# Mini-MLL_Plus_v0_3.net
KiCad netlist of a schematic drawn in EAGLE
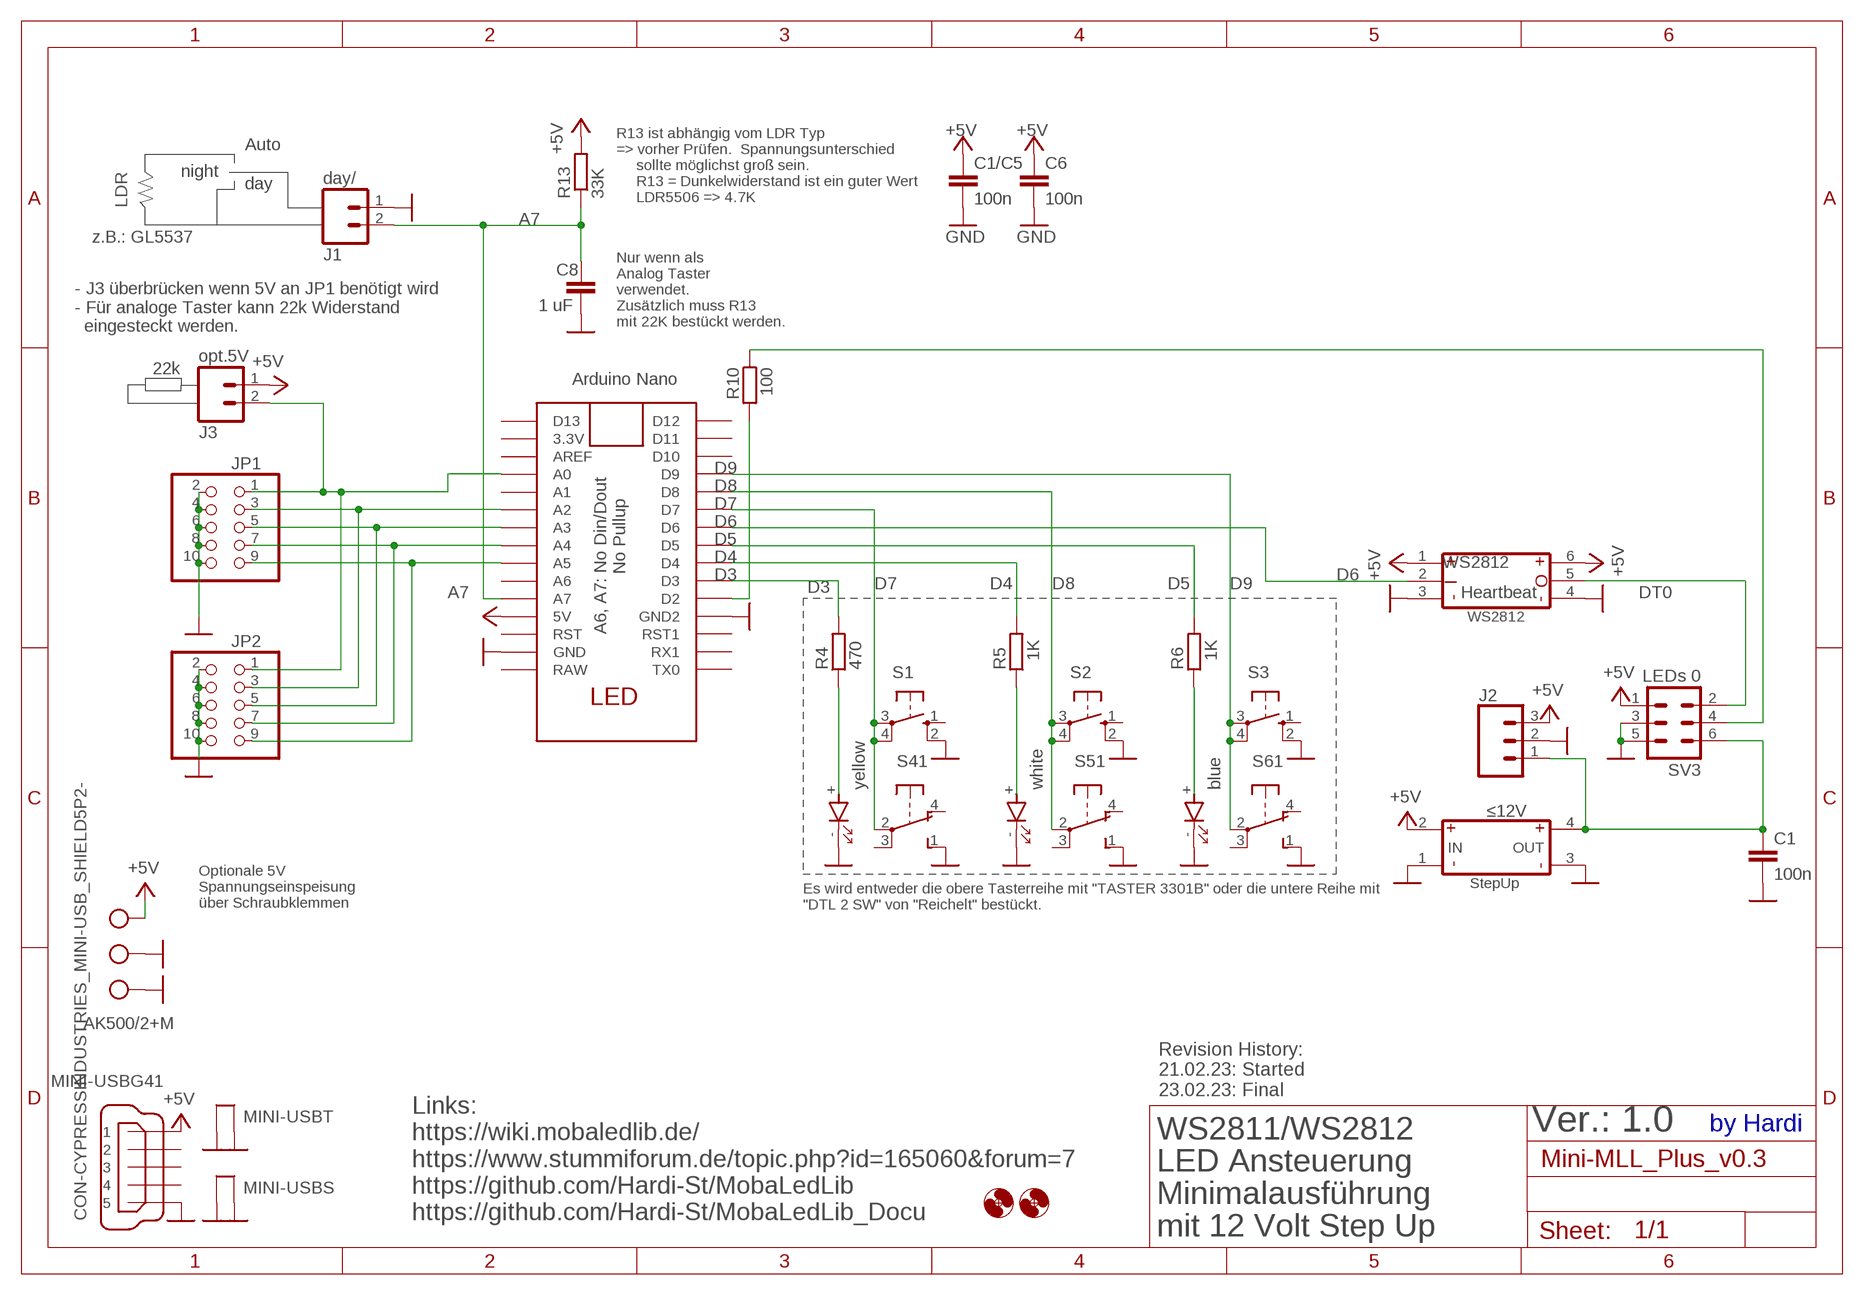
[diagram p0: schematic, sheet 1]

(export (version "E")
  (design (tool "Eeschema 10.0.6"))
  (components
    (comp (ref "C1")
      (value "100n")
      (footprint "eagle-import:C025-025X050")
      (libsource (lib "eagle-import") (part "C-EU025-025X050"))
    )
    (comp (ref "C1/C5")
      (value "100n")
      (footprint "eagle-import:C025-025X050")
      (libsource (lib "eagle-import") (part "C-EU025-025X050"))
    )
    (comp (ref "C6")
      (value "100n")
      (footprint "eagle-import:C025-025X050")
      (libsource (lib "eagle-import") (part "C-EU025-025X050"))
    )
    (comp (ref "C8")
      (value "1 uF")
      (footprint "eagle-import:C025-025X050")
      (libsource (lib "eagle-import") (part "C-EU025-025X050"))
    )
    (comp (ref "H1")
      (value "MOUNT-HOLE3.0")
      (footprint "eagle-import:3,0")
      (libsource (lib "eagle-import") (part "MOUNT-HOLE3.0"))
    )
    (comp (ref "H2")
      (value "MOUNT-HOLE3.0")
      (footprint "eagle-import:3,0")
      (libsource (lib "eagle-import") (part "MOUNT-HOLE3.0"))
    )
    (comp (ref "J1")
      (value "day/")
      (footprint "eagle-import:1X02")
      (libsource (lib "eagle-import") (part "M02PTH"))
    )
    (comp (ref "J2")
      (value "CONN_03")
      (footprint "eagle-import:1X03")
      (libsource (lib "eagle-import") (part "CONN_03"))
    )
    (comp (ref "J3")
      (value "opt.5V")
      (footprint "eagle-import:1X02")
      (libsource (lib "eagle-import") (part "M02PTH"))
    )
    (comp (ref "JP1")
      (value "PINHD-2X5/90")
      (footprint "eagle-import:2X05_90")
      (libsource (lib "eagle-import") (part "PINHD-2X5/90"))
    )
    (comp (ref "JP2")
      (value "PINHD-2X5CLEAR")
      (footprint "eagle-import:2X05_90_CL")
      (libsource (lib "eagle-import") (part "PINHD-2X5CLEAR"))
    )
    (comp (ref "MINI-USB")
      (value "CON-CYPRESSINDUSTRIES_MINI-USB_SHIELD5P2-")
      (footprint "eagle-import:MINI_USB_MULTI")
      (libsource (lib "eagle-import") (part "CON-CYPRESSINDUSTRIES_MINI-USB_SHIELD5P2-"))
    )
    (comp (ref "R4")
      (value "470")
      (footprint "eagle-import:0204_7")
      (libsource (lib "eagle-import") (part "R0204/7"))
    )
    (comp (ref "R5")
      (value "1K")
      (footprint "eagle-import:0204_7")
      (libsource (lib "eagle-import") (part "R0204/7"))
    )
    (comp (ref "R6")
      (value "1K")
      (footprint "eagle-import:0204_7")
      (libsource (lib "eagle-import") (part "R0204/7"))
    )
    (comp (ref "R10")
      (value "100")
      (footprint "eagle-import:0207_2V")
      (libsource (lib "eagle-import") (part "R-EU_0207/2V"))
    )
    (comp (ref "R13")
      (value "33K")
      (footprint "eagle-import:0204_7")
      (libsource (lib "eagle-import") (part "R0204/7"))
    )
    (comp (ref "S1")
      (value "10-XX")
      (footprint "eagle-import:B3F-10XX")
      (fields (field (name "MPN") "B3F-1000"))
      (libsource (lib "eagle-import") (part "10-XX"))
    )
    (comp (ref "S2")
      (value "10-XX")
      (footprint "eagle-import:B3F-10XX")
      (fields (field (name "MPN") "B3F-1000"))
      (libsource (lib "eagle-import") (part "10-XX"))
    )
    (comp (ref "S3")
      (value "10-XX")
      (footprint "eagle-import:B3F-10XX")
      (fields (field (name "MPN") "B3F-1000"))
      (libsource (lib "eagle-import") (part "10-XX"))
    )
    (comp (ref "S4")
      (value "yellow")
      (footprint "eagle-import:SRKL")
      (libsource (lib "eagle-import") (part "SRKL"))
    )
    (comp (ref "S5")
      (value "white")
      (footprint "eagle-import:SRKL")
      (libsource (lib "eagle-import") (part "SRKL"))
    )
    (comp (ref "S6")
      (value "blue")
      (footprint "eagle-import:SRKL")
      (libsource (lib "eagle-import") (part "SRKL"))
    )
    (comp (ref "SV3")
      (value "LEDs 0")
      (footprint "eagle-import:ML6")
      (libsource (lib "eagle-import") (part "ML6"))
    )
    (comp (ref "U2")
      (value "LED NANO")
      (footprint "eagle-import:NANO")
      (libsource (lib "eagle-import") (part "NANO"))
    )
    (comp (ref "WS2812")
      (value "WS2812_BREAKOUT")
      (footprint "eagle-import:WS2812__BREAKOUT")
      (libsource (lib "eagle-import") (part "WS2812_BREAKOUT"))
    )
    (comp (ref "X4")
      (value "AK500/2+M")
      (footprint "eagle-import:AK500_2+M")
      (libsource (lib "eagle-import") (part "AK500/2+M"))
    )
    (comp (ref "≤12V")
      (value "STEP_UP")
      (footprint "eagle-import:MINI_STEP_UP")
      (libsource (lib "eagle-import") (part "STEP_UP"))
    )
  )
  (nets
    (net (code "1") (name "+5V") (class "Default")
      (node (ref "C1/C5") (pin "1") (pinfunction "1_1") (pintype "passive"))
      (node (ref "C6") (pin "1") (pinfunction "1_1") (pintype "passive"))
      (node (ref "J2") (pin "3") (pinfunction "3_3") (pintype "passive"))
      (node (ref "J3") (pin "1") (pinfunction "1_1") (pintype "passive"))
      (node (ref "MINI-USB") (pin "1") (pinfunction "1_1") (pintype "passive"))
      (node (ref "R13") (pin "2") (pinfunction "2_2") (pintype "passive"))
      (node (ref "SV3") (pin "1") (pinfunction "1_1") (pintype "passive"))
      (node (ref "U2") (pin "5V") (pinfunction "5V_5V") (pintype "bidirectional"))
      (node (ref "WS2812") (pin "1") (pinfunction "VDD1_1") (pintype "passive"))
      (node (ref "WS2812") (pin "6") (pinfunction "VDD_6") (pintype "passive"))
      (node (ref "X4") (pin "2") (pinfunction "KL_2") (pintype "passive"))
      (node (ref "≤12V") (pin "2") (pinfunction "VDD_IN_2") (pintype "passive"))
    )
    (net (code "2") (name "/A7") (class "Default")
      (node (ref "C8") (pin "1") (pinfunction "1_1") (pintype "passive"))
      (node (ref "J1") (pin "2") (pinfunction "2_2") (pintype "passive"))
      (node (ref "R13") (pin "1") (pinfunction "1_1") (pintype "passive"))
      (node (ref "U2") (pin "A7") (pinfunction "A7_A7") (pintype "bidirectional"))
    )
    (net (code "3") (name "/D3") (class "Default")
      (node (ref "R4") (pin "2") (pinfunction "2_2") (pintype "passive"))
      (node (ref "U2") (pin "D3") (pinfunction "D3_D3") (pintype "bidirectional"))
    )
    (net (code "4") (name "/D4") (class "Default")
      (node (ref "R5") (pin "2") (pinfunction "2_2") (pintype "passive"))
      (node (ref "U2") (pin "D4") (pinfunction "D4_D4") (pintype "bidirectional"))
    )
    (net (code "5") (name "/D5") (class "Default")
      (node (ref "R6") (pin "2") (pinfunction "2_2") (pintype "passive"))
      (node (ref "U2") (pin "D5") (pinfunction "D5_D5") (pintype "bidirectional"))
    )
    (net (code "6") (name "/D6") (class "Default")
      (node (ref "U2") (pin "D6") (pinfunction "D6_D6") (pintype "bidirectional"))
      (node (ref "WS2812") (pin "2") (pinfunction "DIN_2") (pintype "passive"))
    )
    (net (code "7") (name "/D7") (class "Default")
      (node (ref "S1") (pin "3") (pinfunction "P_3") (pintype "passive"))
      (node (ref "S1") (pin "4") (pinfunction "P1_4") (pintype "passive"))
      (node (ref "S4") (pin "2") (pinfunction "P_2") (pintype "passive"))
      (node (ref "U2") (pin "D7") (pinfunction "D7_D7") (pintype "bidirectional"))
    )
    (net (code "8") (name "/D8") (class "Default")
      (node (ref "S2") (pin "3") (pinfunction "P_3") (pintype "passive"))
      (node (ref "S2") (pin "4") (pinfunction "P1_4") (pintype "passive"))
      (node (ref "S5") (pin "2") (pinfunction "P_2") (pintype "passive"))
      (node (ref "U2") (pin "D8") (pinfunction "D8_D8") (pintype "bidirectional"))
    )
    (net (code "9") (name "/D9") (class "Default")
      (node (ref "S3") (pin "3") (pinfunction "P_3") (pintype "passive"))
      (node (ref "S3") (pin "4") (pinfunction "P1_4") (pintype "passive"))
      (node (ref "S6") (pin "2") (pinfunction "P_2") (pintype "passive"))
      (node (ref "U2") (pin "D9") (pinfunction "D9_D9") (pintype "bidirectional"))
    )
    (net (code "10") (name "/DT0") (class "Default")
      (node (ref "SV3") (pin "2") (pinfunction "2_2") (pintype "passive"))
      (node (ref "WS2812") (pin "5") (pinfunction "DO_5") (pintype "passive"))
    )
    (net (code "11") (name "GND") (class "Default")
      (node (ref "C1") (pin "2") (pinfunction "2_2") (pintype "passive"))
      (node (ref "C1/C5") (pin "2") (pinfunction "2_2") (pintype "passive"))
      (node (ref "C6") (pin "2") (pinfunction "2_2") (pintype "passive"))
      (node (ref "C8") (pin "2") (pinfunction "2_2") (pintype "passive"))
      (node (ref "J1") (pin "1") (pinfunction "1_1") (pintype "passive"))
      (node (ref "J2") (pin "2") (pinfunction "2_2") (pintype "passive"))
      (node (ref "JP1") (pin "10") (pinfunction "10_10") (pintype "passive"))
      (node (ref "JP1") (pin "2") (pinfunction "2_2") (pintype "passive"))
      (node (ref "JP1") (pin "4") (pinfunction "4_4") (pintype "passive"))
      (node (ref "JP1") (pin "6") (pinfunction "6_6") (pintype "passive"))
      (node (ref "JP1") (pin "8") (pinfunction "8_8") (pintype "passive"))
      (node (ref "JP2") (pin "10") (pinfunction "10_10") (pintype "passive"))
      (node (ref "JP2") (pin "2") (pinfunction "2_2") (pintype "passive"))
      (node (ref "JP2") (pin "4") (pinfunction "4_4") (pintype "passive"))
      (node (ref "JP2") (pin "6") (pinfunction "6_6") (pintype "passive"))
      (node (ref "JP2") (pin "8") (pinfunction "8_8") (pintype "passive"))
      (node (ref "MINI-USB") (pin "5") (pinfunction "5_5") (pintype "passive"))
      (node (ref "MINI-USB") (pin "M1") (pinfunction "S1_M1") (pintype "passive"))
      (node (ref "MINI-USB") (pin "M2") (pinfunction "S2_M2") (pintype "passive"))
      (node (ref "MINI-USB") (pin "M3") (pinfunction "S1_M3") (pintype "passive"))
      (node (ref "MINI-USB") (pin "M4") (pinfunction "S2_M4") (pintype "passive"))
      (node (ref "S1") (pin "2") (pinfunction "S1_2") (pintype "passive"))
      (node (ref "S2") (pin "2") (pinfunction "S1_2") (pintype "passive"))
      (node (ref "S3") (pin "2") (pinfunction "S1_2") (pintype "passive"))
      (node (ref "S4") (pin "-") (pinfunction "C_-") (pintype "passive"))
      (node (ref "S4") (pin "1") (pinfunction "S_1") (pintype "passive"))
      (node (ref "S5") (pin "-") (pinfunction "C_-") (pintype "passive"))
      (node (ref "S5") (pin "1") (pinfunction "S_1") (pintype "passive"))
      (node (ref "S6") (pin "-") (pinfunction "C_-") (pintype "passive"))
      (node (ref "S6") (pin "1") (pinfunction "S_1") (pintype "passive"))
      (node (ref "SV3") (pin "3") (pinfunction "3_3") (pintype "passive"))
      (node (ref "SV3") (pin "5") (pinfunction "5_5") (pintype "passive"))
      (node (ref "U2") (pin "GND") (pinfunction "GND_GND") (pintype "bidirectional"))
      (node (ref "U2") (pin "GND1") (pinfunction "GND2_GND1") (pintype "bidirectional"))
      (node (ref "WS2812") (pin "3") (pinfunction "GND1_3") (pintype "passive"))
      (node (ref "WS2812") (pin "4") (pinfunction "GND_4") (pintype "passive"))
      (node (ref "X4") (pin "1") (pinfunction "KL_1") (pintype "passive"))
      (node (ref "X4") (pin "M") (pinfunction "KL_M") (pintype "passive"))
      (node (ref "≤12V") (pin "1") (pinfunction "GND_IN_1") (pintype "passive"))
      (node (ref "≤12V") (pin "3") (pinfunction "GND_OUT_3") (pintype "passive"))
    )
    (net (code "12") (name "Net-(J3-Pad2)") (class "Default")
      (node (ref "J3") (pin "2") (pinfunction "2_2") (pintype "passive"))
      (node (ref "JP1") (pin "1") (pinfunction "1_1") (pintype "passive"))
      (node (ref "JP2") (pin "1") (pinfunction "1_1") (pintype "passive"))
      (node (ref "U2") (pin "A0") (pinfunction "A0_A0") (pintype "bidirectional"))
    )
    (net (code "13") (name "Net-(JP1-Pad3)") (class "Default")
      (node (ref "JP1") (pin "3") (pinfunction "3_3") (pintype "passive"))
      (node (ref "JP2") (pin "3") (pinfunction "3_3") (pintype "passive"))
      (node (ref "U2") (pin "A2") (pinfunction "A2_A2") (pintype "bidirectional"))
    )
    (net (code "14") (name "Net-(JP1-Pad5)") (class "Default")
      (node (ref "JP1") (pin "5") (pinfunction "5_5") (pintype "passive"))
      (node (ref "JP2") (pin "5") (pinfunction "5_5") (pintype "passive"))
      (node (ref "U2") (pin "A3") (pinfunction "A3_A3") (pintype "bidirectional"))
    )
    (net (code "15") (name "Net-(JP1-Pad7)") (class "Default")
      (node (ref "JP1") (pin "7") (pinfunction "7_7") (pintype "passive"))
      (node (ref "JP2") (pin "7") (pinfunction "7_7") (pintype "passive"))
      (node (ref "U2") (pin "A4") (pinfunction "A4_A4") (pintype "bidirectional"))
    )
    (net (code "16") (name "Net-(JP1-Pad9)") (class "Default")
      (node (ref "JP1") (pin "9") (pinfunction "9_9") (pintype "passive"))
      (node (ref "JP2") (pin "9") (pinfunction "9_9") (pintype "passive"))
      (node (ref "U2") (pin "A5") (pinfunction "A5_A5") (pintype "bidirectional"))
    )
    (net (code "17") (name "Net-(R10-Pad1)") (class "Default")
      (node (ref "R10") (pin "1") (pinfunction "1_1") (pintype "passive"))
      (node (ref "SV3") (pin "4") (pinfunction "4_4") (pintype "passive"))
    )
    (net (code "18") (name "Net-(R10-Pad2)") (class "Default")
      (node (ref "R10") (pin "2") (pinfunction "2_2") (pintype "passive"))
      (node (ref "U2") (pin "D2") (pinfunction "D2_D2") (pintype "bidirectional"))
    )
    (net (code "19") (name "Net-(S4B-A)") (class "Default")
      (node (ref "R4") (pin "1") (pinfunction "1_1") (pintype "passive"))
      (node (ref "S4") (pin "+") (pinfunction "A_+") (pintype "passive"))
    )
    (net (code "20") (name "Net-(S5B-A)") (class "Default")
      (node (ref "R5") (pin "1") (pinfunction "1_1") (pintype "passive"))
      (node (ref "S5") (pin "+") (pinfunction "A_+") (pintype "passive"))
    )
    (net (code "21") (name "Net-(S6B-A)") (class "Default")
      (node (ref "R6") (pin "1") (pinfunction "1_1") (pintype "passive"))
      (node (ref "S6") (pin "+") (pinfunction "A_+") (pintype "passive"))
    )
    (net (code "22") (name "Net-(≤12V-VDD_OUT)") (class "Default")
      (node (ref "C1") (pin "1") (pinfunction "1_1") (pintype "passive"))
      (node (ref "J2") (pin "1") (pinfunction "1_1") (pintype "passive"))
      (node (ref "SV3") (pin "6") (pinfunction "6_6") (pintype "passive"))
      (node (ref "≤12V") (pin "4") (pinfunction "VDD_OUT_4") (pintype "passive"))
    )
    (net (code "23") (name "unconnected-(MINI-USB-Pad2)") (class "Default")
      (node (ref "MINI-USB") (pin "2") (pinfunction "2_2") (pintype "passive"))
    )
    (net (code "24") (name "unconnected-(MINI-USB-Pad3)") (class "Default")
      (node (ref "MINI-USB") (pin "3") (pinfunction "3_3") (pintype "passive"))
    )
    (net (code "25") (name "unconnected-(MINI-USB-Pad4)") (class "Default")
      (node (ref "MINI-USB") (pin "4") (pinfunction "4_4") (pintype "passive"))
    )
    (net (code "26") (name "unconnected-(S1-S-Pad1)") (class "Default")
      (node (ref "S1") (pin "1") (pinfunction "S_1") (pintype "passive"))
    )
    (net (code "27") (name "unconnected-(S2-S-Pad1)") (class "Default")
      (node (ref "S2") (pin "1") (pinfunction "S_1") (pintype "passive"))
    )
    (net (code "28") (name "unconnected-(S3-S-Pad1)") (class "Default")
      (node (ref "S3") (pin "1") (pinfunction "S_1") (pintype "passive"))
    )
    (net (code "29") (name "unconnected-(S4A-O-Pad4)") (class "Default")
      (node (ref "S4") (pin "4") (pinfunction "O_4") (pintype "passive"))
    )
    (net (code "30") (name "unconnected-(S4A-P-Pad3)") (class "Default")
      (node (ref "S4") (pin "3") (pinfunction "P_3") (pintype "passive"))
    )
    (net (code "31") (name "unconnected-(S5A-O-Pad4)") (class "Default")
      (node (ref "S5") (pin "4") (pinfunction "O_4") (pintype "passive"))
    )
    (net (code "32") (name "unconnected-(S5A-P-Pad3)") (class "Default")
      (node (ref "S5") (pin "3") (pinfunction "P_3") (pintype "passive"))
    )
    (net (code "33") (name "unconnected-(S6A-O-Pad4)") (class "Default")
      (node (ref "S6") (pin "4") (pinfunction "O_4") (pintype "passive"))
    )
    (net (code "34") (name "unconnected-(S6A-P-Pad3)") (class "Default")
      (node (ref "S6") (pin "3") (pinfunction "P_3") (pintype "passive"))
    )
    (net (code "35") (name "unconnected-(U2-Pad3.3V)") (class "Default")
      (node (ref "U2") (pin "3.3V") (pinfunction "3.3V_3.3V") (pintype "bidirectional"))
    )
    (net (code "36") (name "unconnected-(U2-PadA1)") (class "Default")
      (node (ref "U2") (pin "A1") (pinfunction "A1_A1") (pintype "bidirectional"))
    )
    (net (code "37") (name "unconnected-(U2-PadA6)") (class "Default")
      (node (ref "U2") (pin "A6") (pinfunction "A6_A6") (pintype "bidirectional"))
    )
    (net (code "38") (name "unconnected-(U2-PadAREF)") (class "Default")
      (node (ref "U2") (pin "AREF") (pinfunction "AREF_AREF") (pintype "bidirectional"))
    )
    (net (code "39") (name "unconnected-(U2-PadD10)") (class "Default")
      (node (ref "U2") (pin "D10") (pinfunction "D10_D10") (pintype "bidirectional"))
    )
    (net (code "40") (name "unconnected-(U2-PadD11)") (class "Default")
      (node (ref "U2") (pin "D11") (pinfunction "D11_D11") (pintype "bidirectional"))
    )
    (net (code "41") (name "unconnected-(U2-PadD12)") (class "Default")
      (node (ref "U2") (pin "D12") (pinfunction "D12_D12") (pintype "bidirectional"))
    )
    (net (code "42") (name "unconnected-(U2-PadD13)") (class "Default")
      (node (ref "U2") (pin "D13") (pinfunction "D13_D13") (pintype "bidirectional"))
    )
    (net (code "43") (name "unconnected-(U2-PadRAW)") (class "Default")
      (node (ref "U2") (pin "RAW") (pinfunction "RAW_RAW") (pintype "bidirectional"))
    )
    (net (code "44") (name "unconnected-(U2-PadRST)") (class "Default")
      (node (ref "U2") (pin "RST") (pinfunction "RST_RST") (pintype "bidirectional"))
    )
    (net (code "45") (name "unconnected-(U2-PadRST1)") (class "Default")
      (node (ref "U2") (pin "RST1") (pinfunction "RST1_RST1") (pintype "bidirectional"))
    )
    (net (code "46") (name "unconnected-(U2-PadRX1)") (class "Default")
      (node (ref "U2") (pin "RX1") (pinfunction "RX1_RX1") (pintype "bidirectional"))
    )
    (net (code "47") (name "unconnected-(U2-PadTX0)") (class "Default")
      (node (ref "U2") (pin "TX0") (pinfunction "TX0_TX0") (pintype "bidirectional"))
    )
  )
)
